# Motion-Sensor-Sheet.net
KiCad netlist of a schematic drawn in Altium Designer
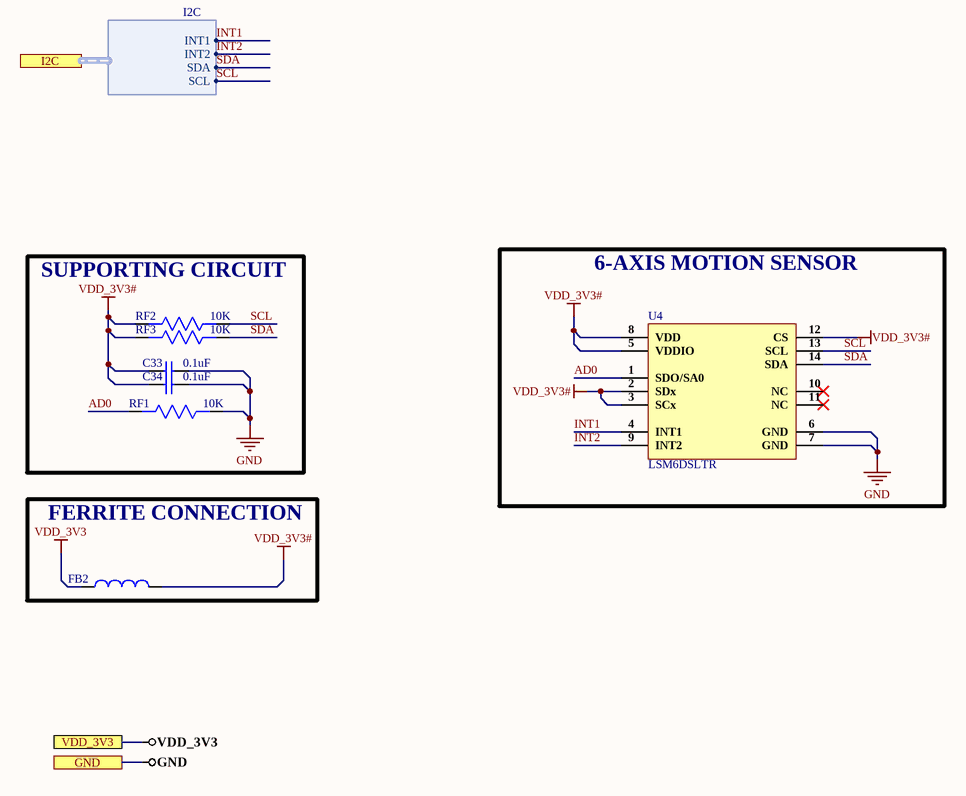
[diagram p0: Motion-Sensor-Sheet.SchDoc]

(export (version "E")
  (design (tool "Eeschema 10.0.6"))
  (components
    (comp (ref "C33")
      (value "0.1uF")
      (footprint "Cap0603")
      (description "Cap Ceramic 0.1uF 50VDC X7R 10% SMD 0603 Paper T/R")
      (fields
        (field (name "MANUFACTURER") "Samsung")
        (field (name "MANUFACTURER PART NUMBER") "CL10B104KB8NNNC")
      )
      (libsource (lib "Cole_Benson") (part "CL10B104KB8NNNC"))
    )
    (comp (ref "C34")
      (value "0.1uF")
      (footprint "Cap0603")
      (description "Cap Ceramic 0.1uF 50VDC X7R 10% SMD 0603 Paper T/R")
      (fields
        (field (name "MANUFACTURER") "Samsung")
        (field (name "MANUFACTURER PART NUMBER") "CL10B104KB8NNNC")
      )
      (libsource (lib "Cole_Benson") (part "CL10B104KB8NNNC"))
    )
    (comp (ref "FB2")
      (value "MPZ1608S121ATDH5")
      (footprint "MPZ1608S121ATDH5")
      (description "Ferrite Beads Multi-Layer 120Ohm 25% 100MHz 2A 45mOhm DCR 0603 Automotive T/R")
      (fields (field (name "MANUFACTURER") "TDK") (field (name "TOLERANCE") "25%"))
      (libsource (lib "Cole_Benson") (part "MPZ1608S121ATDH5"))
    )
    (comp (ref "RF1")
      (value "10K")
      (footprint "Res0603")
      (description "RES SMD 10K Ohm 1% 1/10W 0603")
      (fields
        (field (name "MANUFACTURER") "Yageo")
        (field (name "MANUFACTURER PART NUMBER") "RC0603FR-0710KL")
      )
      (libsource (lib "Cole_Benson") (part "RC0603FR-0710KL"))
    )
    (comp (ref "RF2")
      (value "10K")
      (footprint "Res0603")
      (description "RES SMD 10K Ohm 1% 1/10W 0603")
      (fields
        (field (name "MANUFACTURER") "Yageo")
        (field (name "MANUFACTURER PART NUMBER") "RC0603FR-0710KL")
      )
      (libsource (lib "Cole_Benson") (part "RC0603FR-0710KL"))
    )
    (comp (ref "RF3")
      (value "10K")
      (footprint "Res0603")
      (description "RES SMD 10K Ohm 1% 1/10W 0603")
      (fields
        (field (name "MANUFACTURER") "Yageo")
        (field (name "MANUFACTURER PART NUMBER") "RC0603FR-0710KL")
      )
      (libsource (lib "Cole_Benson") (part "RC0603FR-0710KL"))
    )
    (comp (ref "U4")
      (value "LSM6DSLTR")
      (footprint "14 LGA (2.5x3)")
      (description "IMUACCEL/GYROI2C/SPI14LGA")
      (fields (field (name "MANUFACTURER") "STMicroelectronics") (field (name "LCSC PART NUMBER") "C126672"))
      (libsource (lib "Cole_Benson") (part "LSM6DSLTR"))
    )
  )
  (nets
    (net (code "2") (name "/AD0") (class "Default")
      (node (ref "RF1") (pin "2") (pintype "passive"))
      (node (ref "U4") (pin "1") (pinfunction "SDO/SA0_1") (pintype "passive"))
    )
    (net (code "3") (name "/INT1") (class "Default")
      (node (ref "U4") (pin "4") (pinfunction "INT1_4") (pintype "passive"))
    )
    (net (code "4") (name "/INT2") (class "Default")
      (node (ref "U4") (pin "9") (pinfunction "INT2_9") (pintype "passive"))
    )
    (net (code "5") (name "/SCL") (class "Default")
      (node (ref "RF2") (pin "1") (pintype "passive"))
      (node (ref "U4") (pin "13") (pinfunction "SCL_13") (pintype "passive"))
    )
    (net (code "6") (name "/SDA") (class "Default")
      (node (ref "RF3") (pin "1") (pintype "passive"))
      (node (ref "U4") (pin "14") (pinfunction "SDA_14") (pintype "passive"))
    )
    (net (code "8") (name "GND") (class "Default")
      (node (ref "C33") (pin "2") (pinfunction "2_2") (pintype "passive"))
      (node (ref "C34") (pin "2") (pinfunction "2_2") (pintype "passive"))
      (node (ref "RF1") (pin "1") (pintype "passive"))
      (node (ref "U4") (pin "6") (pinfunction "GND_6") (pintype "passive"))
      (node (ref "U4") (pin "7") (pinfunction "GND_7") (pintype "passive"))
    )
    (net (code "9") (name "VDD_3V3") (class "Default")
      (node (ref "FB2") (pin "1") (pinfunction "1_1") (pintype "passive"))
    )
    (net (code "10") (name "VDD_3V3#") (class "Default")
      (node (ref "C33") (pin "1") (pinfunction "1_1") (pintype "passive"))
      (node (ref "C34") (pin "1") (pinfunction "1_1") (pintype "passive"))
      (node (ref "FB2") (pin "2") (pinfunction "2_2") (pintype "passive"))
      (node (ref "RF2") (pin "2") (pintype "passive"))
      (node (ref "RF3") (pin "2") (pintype "passive"))
      (node (ref "U4") (pin "12") (pinfunction "CS_12") (pintype "passive"))
      (node (ref "U4") (pin "2") (pinfunction "SDx_2") (pintype "passive"))
      (node (ref "U4") (pin "3") (pinfunction "SCx_3") (pintype "passive"))
      (node (ref "U4") (pin "5") (pinfunction "VDDIO_5") (pintype "passive"))
      (node (ref "U4") (pin "8") (pinfunction "VDD_8") (pintype "passive"))
    )
    (net (code "11") (name "unconnected-(U4-NC-Pad10)") (class "Default")
      (node (ref "U4") (pin "10") (pinfunction "NC_10") (pintype "passive+no_connect"))
    )
    (net (code "12") (name "unconnected-(U4-NC-Pad11)") (class "Default")
      (node (ref "U4") (pin "11") (pinfunction "NC_11") (pintype "passive+no_connect"))
    )
  )
)
